# monoblink_pannel.net
KiCad netlist of a schematic drawn in EAGLE
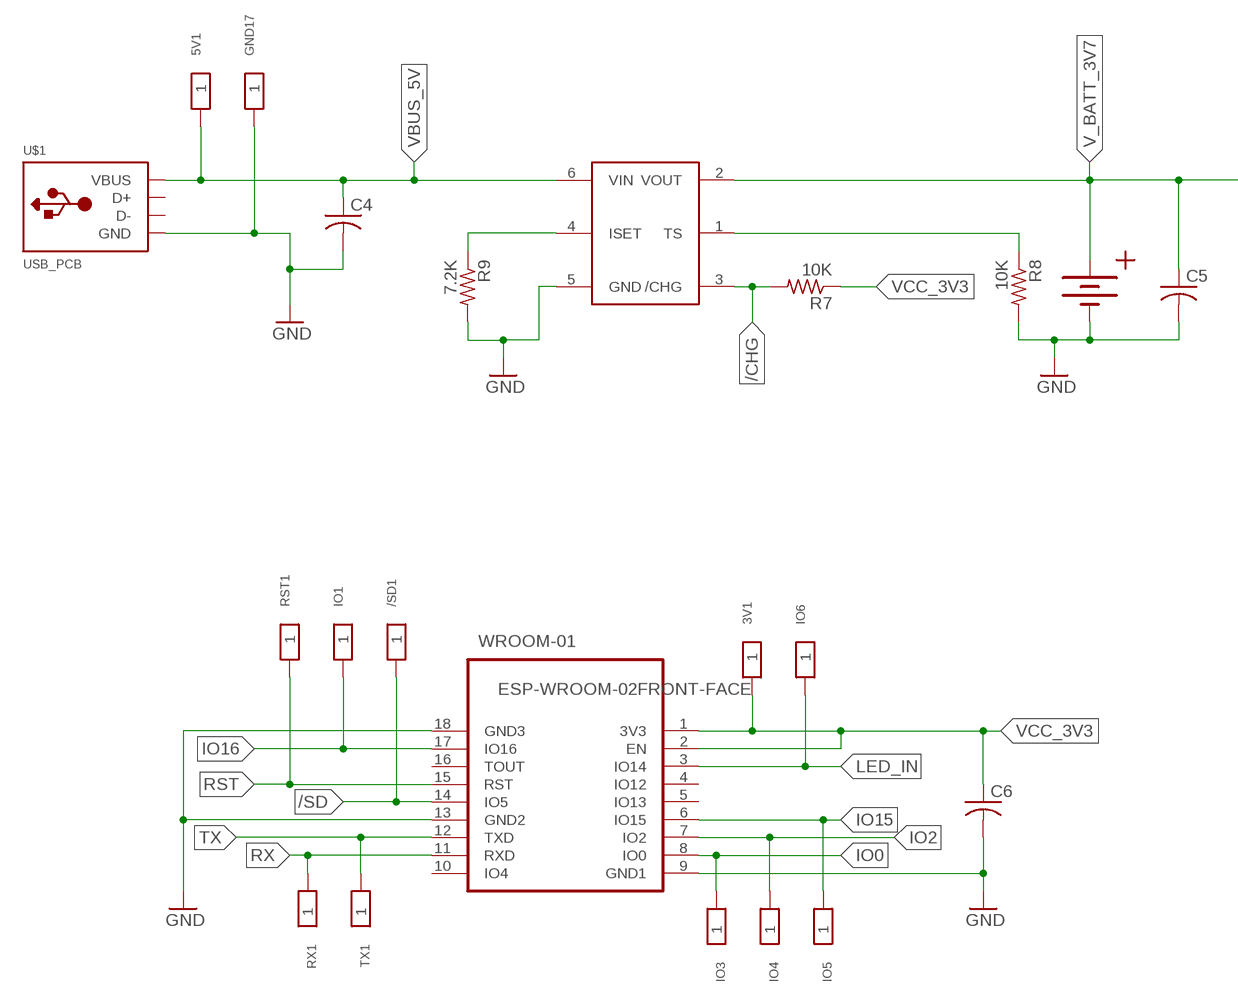
[diagram p0: schematic, sheet 1, part 1 of 2]
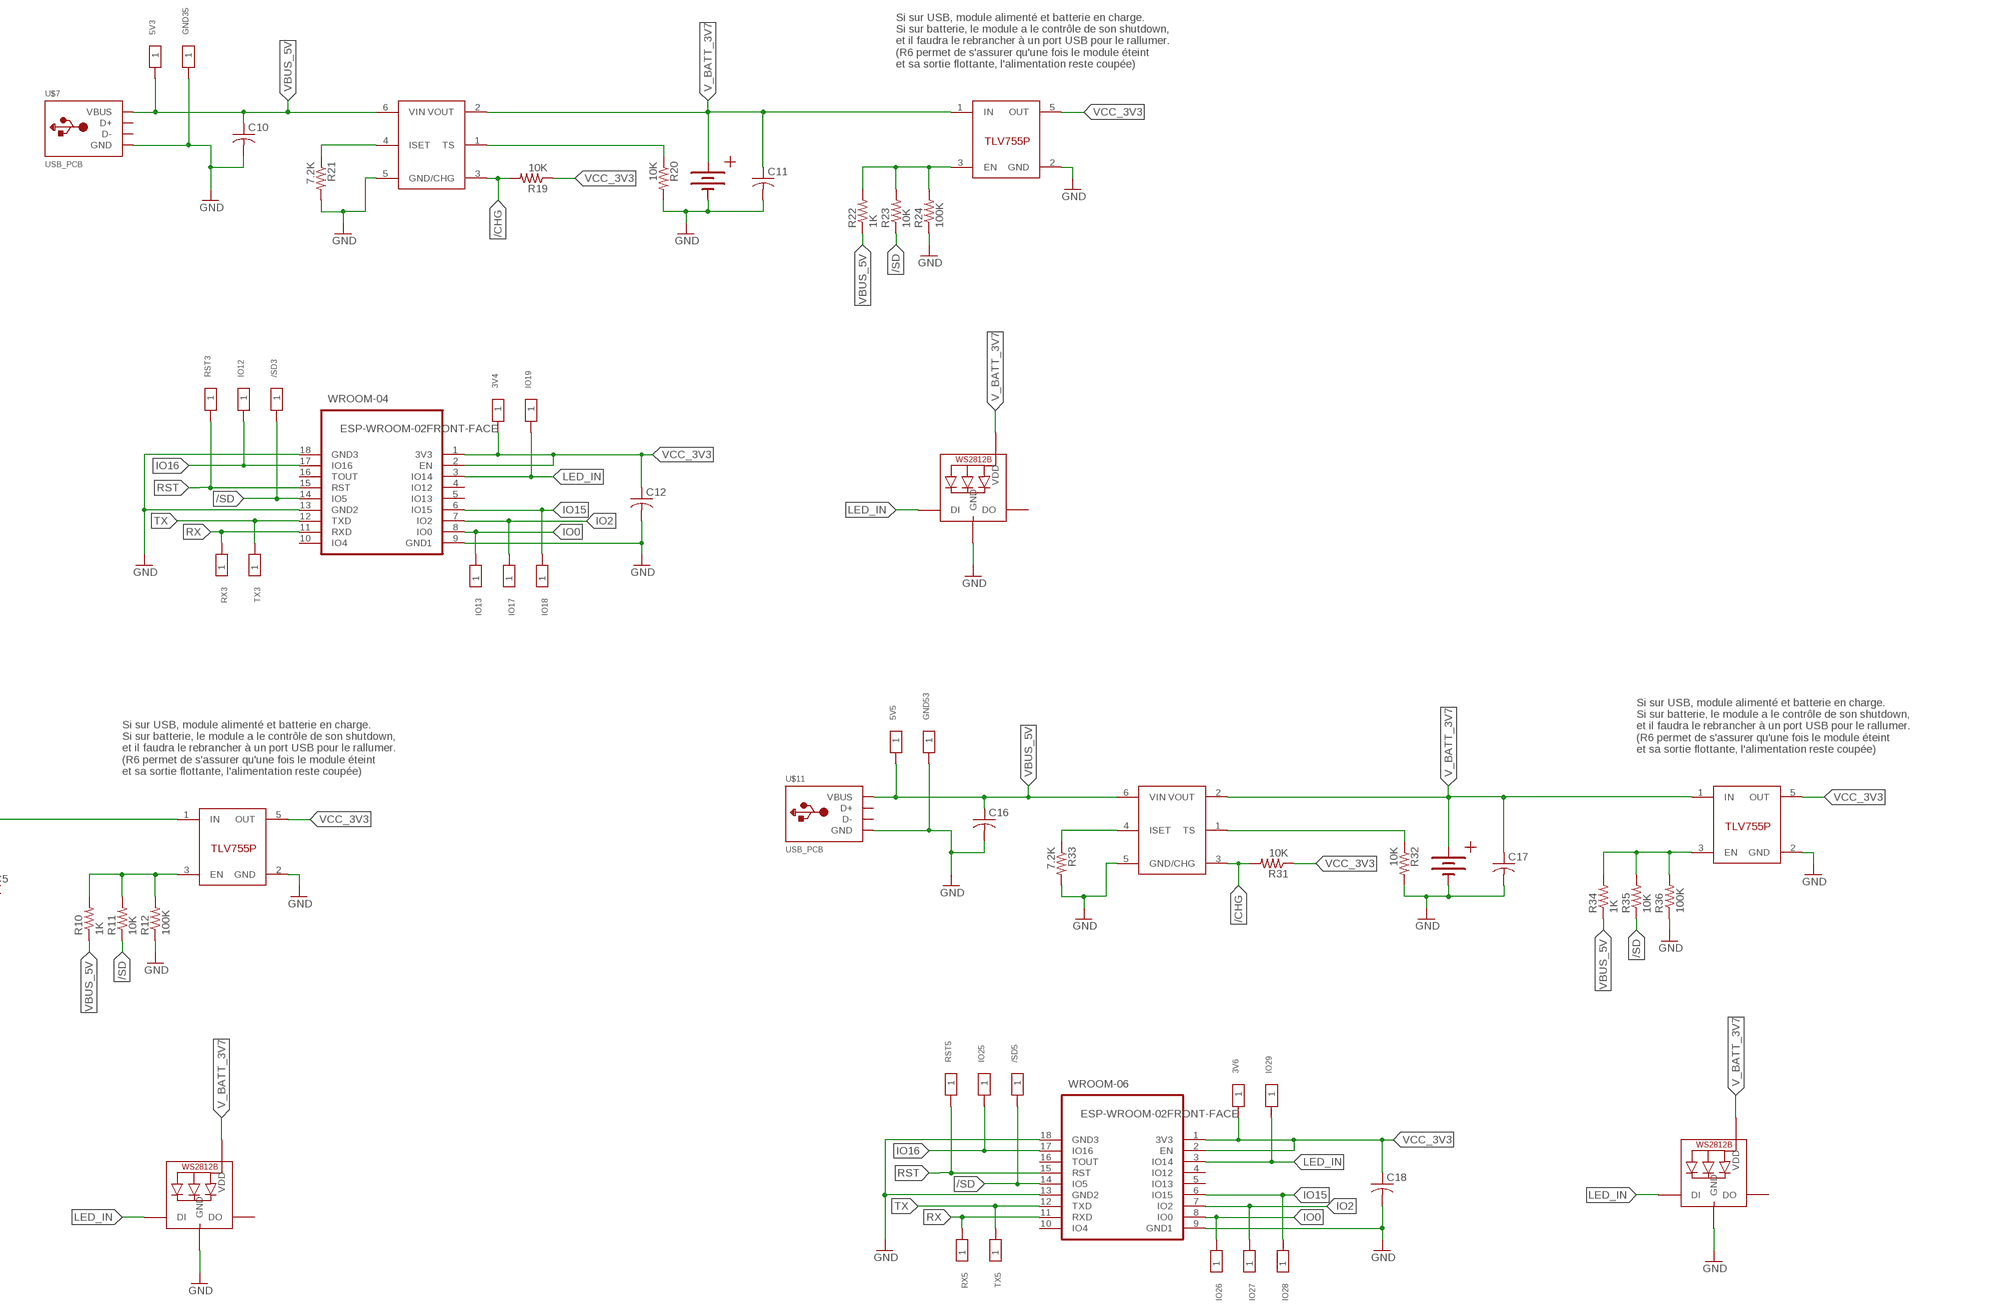
[diagram p1: schematic, sheet 1, part 2 of 2]

(export (version "E")
  (design (tool "Eeschema 10.0.6"))
  (components
    (comp (ref "/SD1")
      (value "TESTPAD_PROG")
      (footprint "eagle-import:TP1.5MM")
      (libsource (lib "eagle-import") (part "TESTPAD_PROG"))
    )
    (comp (ref "/SD3")
      (value "TESTPAD_PROG")
      (footprint "eagle-import:TP1.5MM")
      (libsource (lib "eagle-import") (part "TESTPAD_PROG"))
    )
    (comp (ref "/SD5")
      (value "TESTPAD_PROG")
      (footprint "eagle-import:TP1.5MM")
      (libsource (lib "eagle-import") (part "TESTPAD_PROG"))
    )
    (comp (ref "3V1")
      (value "TESTPAD_PROG")
      (footprint "eagle-import:TP1.5MM")
      (libsource (lib "eagle-import") (part "TESTPAD_PROG"))
    )
    (comp (ref "3V4")
      (value "TESTPAD_PROG")
      (footprint "eagle-import:TP1.5MM")
      (libsource (lib "eagle-import") (part "TESTPAD_PROG"))
    )
    (comp (ref "3V6")
      (value "TESTPAD_PROG")
      (footprint "eagle-import:TP1.5MM")
      (libsource (lib "eagle-import") (part "TESTPAD_PROG"))
    )
    (comp (ref "5V1")
      (value "TESTPAD_PROG")
      (footprint "eagle-import:TP1.5MM")
      (libsource (lib "eagle-import") (part "TESTPAD_PROG"))
    )
    (comp (ref "5V3")
      (value "TESTPAD_PROG")
      (footprint "eagle-import:TP1.5MM")
      (libsource (lib "eagle-import") (part "TESTPAD_PROG"))
    )
    (comp (ref "5V5")
      (value "TESTPAD_PROG")
      (footprint "eagle-import:TP1.5MM")
      (libsource (lib "eagle-import") (part "TESTPAD_PROG"))
    )
    (comp (ref "C4")
      (value "C-USC0603")
      (footprint "eagle-import:C0603")
      (libsource (lib "eagle-import") (part "C-USC0603"))
    )
    (comp (ref "C5")
      (value "C-USC0603")
      (footprint "eagle-import:C0603")
      (libsource (lib "eagle-import") (part "C-USC0603"))
    )
    (comp (ref "C6")
      (value "C-USC0603")
      (footprint "eagle-import:C0603")
      (libsource (lib "eagle-import") (part "C-USC0603"))
    )
    (comp (ref "C10")
      (value "C-USC0603")
      (footprint "eagle-import:C0603")
      (libsource (lib "eagle-import") (part "C-USC0603"))
    )
    (comp (ref "C11")
      (value "C-USC0603")
      (footprint "eagle-import:C0603")
      (libsource (lib "eagle-import") (part "C-USC0603"))
    )
    (comp (ref "C12")
      (value "C-USC0603")
      (footprint "eagle-import:C0603")
      (libsource (lib "eagle-import") (part "C-USC0603"))
    )
    (comp (ref "C16")
      (value "C-USC0603")
      (footprint "eagle-import:C0603")
      (libsource (lib "eagle-import") (part "C-USC0603"))
    )
    (comp (ref "C17")
      (value "C-USC0603")
      (footprint "eagle-import:C0603")
      (libsource (lib "eagle-import") (part "C-USC0603"))
    )
    (comp (ref "C18")
      (value "C-USC0603")
      (footprint "eagle-import:C0603")
      (libsource (lib "eagle-import") (part "C-USC0603"))
    )
    (comp (ref "CHG1")
      (value "BQ21040")
      (footprint "eagle-import:SOT23-6")
      (libsource (lib "eagle-import") (part "BQ21040"))
    )
    (comp (ref "CHG3")
      (value "BQ21040")
      (footprint "eagle-import:SOT23-6")
      (libsource (lib "eagle-import") (part "BQ21040"))
    )
    (comp (ref "CHG5")
      (value "BQ21040")
      (footprint "eagle-import:SOT23-6")
      (libsource (lib "eagle-import") (part "BQ21040"))
    )
    (comp (ref "GND17")
      (value "TESTPAD_PROG")
      (footprint "eagle-import:TP1.5MM")
      (libsource (lib "eagle-import") (part "TESTPAD_PROG"))
    )
    (comp (ref "GND35")
      (value "TESTPAD_PROG")
      (footprint "eagle-import:TP1.5MM")
      (libsource (lib "eagle-import") (part "TESTPAD_PROG"))
    )
    (comp (ref "GND53")
      (value "TESTPAD_PROG")
      (footprint "eagle-import:TP1.5MM")
      (libsource (lib "eagle-import") (part "TESTPAD_PROG"))
    )
    (comp (ref "IO1")
      (value "TESTPAD_PROG")
      (footprint "eagle-import:TP1.5MM")
      (libsource (lib "eagle-import") (part "TESTPAD_PROG"))
    )
    (comp (ref "IO3")
      (value "TESTPAD_PROG")
      (footprint "eagle-import:TP1.5MM")
      (libsource (lib "eagle-import") (part "TESTPAD_PROG"))
    )
    (comp (ref "IO4")
      (value "TESTPAD_PROG")
      (footprint "eagle-import:TP1.5MM")
      (libsource (lib "eagle-import") (part "TESTPAD_PROG"))
    )
    (comp (ref "IO5")
      (value "TESTPAD_PROG")
      (footprint "eagle-import:TP1.5MM")
      (libsource (lib "eagle-import") (part "TESTPAD_PROG"))
    )
    (comp (ref "IO6")
      (value "TESTPAD_PROG")
      (footprint "eagle-import:TP1.5MM")
      (libsource (lib "eagle-import") (part "TESTPAD_PROG"))
    )
    (comp (ref "IO12")
      (value "TESTPAD_PROG")
      (footprint "eagle-import:TP1.5MM")
      (libsource (lib "eagle-import") (part "TESTPAD_PROG"))
    )
    (comp (ref "IO13")
      (value "TESTPAD_PROG")
      (footprint "eagle-import:TP1.5MM")
      (libsource (lib "eagle-import") (part "TESTPAD_PROG"))
    )
    (comp (ref "IO17")
      (value "TESTPAD_PROG")
      (footprint "eagle-import:TP1.5MM")
      (libsource (lib "eagle-import") (part "TESTPAD_PROG"))
    )
    (comp (ref "IO18")
      (value "TESTPAD_PROG")
      (footprint "eagle-import:TP1.5MM")
      (libsource (lib "eagle-import") (part "TESTPAD_PROG"))
    )
    (comp (ref "IO19")
      (value "TESTPAD_PROG")
      (footprint "eagle-import:TP1.5MM")
      (libsource (lib "eagle-import") (part "TESTPAD_PROG"))
    )
    (comp (ref "IO25")
      (value "TESTPAD_PROG")
      (footprint "eagle-import:TP1.5MM")
      (libsource (lib "eagle-import") (part "TESTPAD_PROG"))
    )
    (comp (ref "IO26")
      (value "TESTPAD_PROG")
      (footprint "eagle-import:TP1.5MM")
      (libsource (lib "eagle-import") (part "TESTPAD_PROG"))
    )
    (comp (ref "IO27")
      (value "TESTPAD_PROG")
      (footprint "eagle-import:TP1.5MM")
      (libsource (lib "eagle-import") (part "TESTPAD_PROG"))
    )
    (comp (ref "IO28")
      (value "TESTPAD_PROG")
      (footprint "eagle-import:TP1.5MM")
      (libsource (lib "eagle-import") (part "TESTPAD_PROG"))
    )
    (comp (ref "IO29")
      (value "TESTPAD_PROG")
      (footprint "eagle-import:TP1.5MM")
      (libsource (lib "eagle-import") (part "TESTPAD_PROG"))
    )
    (comp (ref "LDO1")
      (value "TLV755P")
      (footprint "eagle-import:SOT23-5")
      (libsource (lib "eagle-import") (part "TLV755P"))
    )
    (comp (ref "LDO3")
      (value "TLV755P")
      (footprint "eagle-import:SOT23-5")
      (libsource (lib "eagle-import") (part "TLV755P"))
    )
    (comp (ref "LDO5")
      (value "TLV755P")
      (footprint "eagle-import:SOT23-5")
      (libsource (lib "eagle-import") (part "TLV755P"))
    )
    (comp (ref "LED1")
      (value "WS2812B5050")
      (footprint "eagle-import:WS2812B")
      (libsource (lib "eagle-import") (part "WS2812B5050"))
    )
    (comp (ref "LED3")
      (value "WS2812B5050")
      (footprint "eagle-import:WS2812B")
      (libsource (lib "eagle-import") (part "WS2812B5050"))
    )
    (comp (ref "LED5")
      (value "WS2812B5050")
      (footprint "eagle-import:WS2812B")
      (libsource (lib "eagle-import") (part "WS2812B5050"))
    )
    (comp (ref "R7")
      (value "10K")
      (footprint "eagle-import:R0603")
      (libsource (lib "eagle-import") (part "R-US_R0603"))
    )
    (comp (ref "R8")
      (value "10K")
      (footprint "eagle-import:R0603")
      (libsource (lib "eagle-import") (part "R-US_R0603"))
    )
    (comp (ref "R9")
      (value "7.2K")
      (footprint "eagle-import:R0603")
      (libsource (lib "eagle-import") (part "R-US_R0603"))
    )
    (comp (ref "R10")
      (value "1K")
      (footprint "eagle-import:R0603")
      (libsource (lib "eagle-import") (part "R-US_R0603"))
    )
    (comp (ref "R11")
      (value "10K")
      (footprint "eagle-import:R0603")
      (libsource (lib "eagle-import") (part "R-US_R0603"))
    )
    (comp (ref "R12")
      (value "100K")
      (footprint "eagle-import:R0603")
      (libsource (lib "eagle-import") (part "R-US_R0603"))
    )
    (comp (ref "R19")
      (value "10K")
      (footprint "eagle-import:R0603")
      (libsource (lib "eagle-import") (part "R-US_R0603"))
    )
    (comp (ref "R20")
      (value "10K")
      (footprint "eagle-import:R0603")
      (libsource (lib "eagle-import") (part "R-US_R0603"))
    )
    (comp (ref "R21")
      (value "7.2K")
      (footprint "eagle-import:R0603")
      (libsource (lib "eagle-import") (part "R-US_R0603"))
    )
    (comp (ref "R22")
      (value "1K")
      (footprint "eagle-import:R0603")
      (libsource (lib "eagle-import") (part "R-US_R0603"))
    )
    (comp (ref "R23")
      (value "10K")
      (footprint "eagle-import:R0603")
      (libsource (lib "eagle-import") (part "R-US_R0603"))
    )
    (comp (ref "R24")
      (value "100K")
      (footprint "eagle-import:R0603")
      (libsource (lib "eagle-import") (part "R-US_R0603"))
    )
    (comp (ref "R31")
      (value "10K")
      (footprint "eagle-import:R0603")
      (libsource (lib "eagle-import") (part "R-US_R0603"))
    )
    (comp (ref "R32")
      (value "10K")
      (footprint "eagle-import:R0603")
      (libsource (lib "eagle-import") (part "R-US_R0603"))
    )
    (comp (ref "R33")
      (value "7.2K")
      (footprint "eagle-import:R0603")
      (libsource (lib "eagle-import") (part "R-US_R0603"))
    )
    (comp (ref "R34")
      (value "1K")
      (footprint "eagle-import:R0603")
      (libsource (lib "eagle-import") (part "R-US_R0603"))
    )
    (comp (ref "R35")
      (value "10K")
      (footprint "eagle-import:R0603")
      (libsource (lib "eagle-import") (part "R-US_R0603"))
    )
    (comp (ref "R36")
      (value "100K")
      (footprint "eagle-import:R0603")
      (libsource (lib "eagle-import") (part "R-US_R0603"))
    )
    (comp (ref "RST1")
      (value "TESTPAD_PROG")
      (footprint "eagle-import:TP1.5MM")
      (libsource (lib "eagle-import") (part "TESTPAD_PROG"))
    )
    (comp (ref "RST3")
      (value "TESTPAD_PROG")
      (footprint "eagle-import:TP1.5MM")
      (libsource (lib "eagle-import") (part "TESTPAD_PROG"))
    )
    (comp (ref "RST5")
      (value "TESTPAD_PROG")
      (footprint "eagle-import:TP1.5MM")
      (libsource (lib "eagle-import") (part "TESTPAD_PROG"))
    )
    (comp (ref "RX1")
      (value "TESTPAD_PROG")
      (footprint "eagle-import:TP1.5MM")
      (libsource (lib "eagle-import") (part "TESTPAD_PROG"))
    )
    (comp (ref "RX3")
      (value "TESTPAD_PROG")
      (footprint "eagle-import:TP1.5MM")
      (libsource (lib "eagle-import") (part "TESTPAD_PROG"))
    )
    (comp (ref "RX5")
      (value "TESTPAD_PROG")
      (footprint "eagle-import:TP1.5MM")
      (libsource (lib "eagle-import") (part "TESTPAD_PROG"))
    )
    (comp (ref "TX1")
      (value "TESTPAD_PROG")
      (footprint "eagle-import:TP1.5MM")
      (libsource (lib "eagle-import") (part "TESTPAD_PROG"))
    )
    (comp (ref "TX3")
      (value "TESTPAD_PROG")
      (footprint "eagle-import:TP1.5MM")
      (libsource (lib "eagle-import") (part "TESTPAD_PROG"))
    )
    (comp (ref "TX5")
      (value "TESTPAD_PROG")
      (footprint "eagle-import:TP1.5MM")
      (libsource (lib "eagle-import") (part "TESTPAD_PROG"))
    )
    (comp (ref "U$1")
      (value "USB_PCB")
      (footprint "eagle-import:USB_PADS")
      (libsource (lib "eagle-import") (part "USB_PCB"))
    )
    (comp (ref "U$3")
      (value "BATT")
      (footprint "eagle-import:BATT_CON")
      (libsource (lib "eagle-import") (part "BATT"))
    )
    (comp (ref "U$7")
      (value "USB_PCB")
      (footprint "eagle-import:USB_PADS")
      (libsource (lib "eagle-import") (part "USB_PCB"))
    )
    (comp (ref "U$8")
      (value "BATT")
      (footprint "eagle-import:BATT_CON")
      (libsource (lib "eagle-import") (part "BATT"))
    )
    (comp (ref "U$11")
      (value "USB_PCB")
      (footprint "eagle-import:USB_PADS")
      (libsource (lib "eagle-import") (part "USB_PCB"))
    )
    (comp (ref "U$12")
      (value "BATT")
      (footprint "eagle-import:BATT_CON")
      (libsource (lib "eagle-import") (part "BATT"))
    )
    (comp (ref "WROOM-01")
      (value "ESP-WROOM-02FRONT-FACE")
      (footprint "eagle-import:FRONT-FACE")
      (libsource (lib "eagle-import") (part "ESP-WROOM-02FRONT-FACE"))
    )
    (comp (ref "WROOM-04")
      (value "ESP-WROOM-02FRONT-FACE")
      (footprint "eagle-import:FRONT-FACE")
      (libsource (lib "eagle-import") (part "ESP-WROOM-02FRONT-FACE"))
    )
    (comp (ref "WROOM-06")
      (value "ESP-WROOM-02FRONT-FACE")
      (footprint "eagle-import:FRONT-FACE")
      (libsource (lib "eagle-import") (part "ESP-WROOM-02FRONT-FACE"))
    )
  )
  (nets
    (net (code "1") (name "GND") (class "Default")
      (node (ref "C10") (pin "2") (pinfunction "2_2") (pintype "passive"))
      (node (ref "C11") (pin "2") (pinfunction "2_2") (pintype "passive"))
      (node (ref "C12") (pin "2") (pinfunction "2_2") (pintype "passive"))
      (node (ref "C16") (pin "2") (pinfunction "2_2") (pintype "passive"))
      (node (ref "C17") (pin "2") (pinfunction "2_2") (pintype "passive"))
      (node (ref "C18") (pin "2") (pinfunction "2_2") (pintype "passive"))
      (node (ref "C4") (pin "2") (pinfunction "2_2") (pintype "passive"))
      (node (ref "C5") (pin "2") (pinfunction "2_2") (pintype "passive"))
      (node (ref "C6") (pin "2") (pinfunction "2_2") (pintype "passive"))
      (node (ref "CHG1") (pin "5") (pinfunction "GND_5") (pintype "bidirectional"))
      (node (ref "CHG3") (pin "5") (pinfunction "GND_5") (pintype "bidirectional"))
      (node (ref "CHG5") (pin "5") (pinfunction "GND_5") (pintype "bidirectional"))
      (node (ref "GND17") (pin "1") (pinfunction "1_1") (pintype "bidirectional"))
      (node (ref "GND35") (pin "1") (pinfunction "1_1") (pintype "bidirectional"))
      (node (ref "GND53") (pin "1") (pinfunction "1_1") (pintype "bidirectional"))
      (node (ref "LDO1") (pin "2") (pinfunction "GND_2") (pintype "bidirectional"))
      (node (ref "LDO3") (pin "2") (pinfunction "GND_2") (pintype "bidirectional"))
      (node (ref "LDO5") (pin "2") (pinfunction "GND_2") (pintype "bidirectional"))
      (node (ref "LED1") (pin "3-GND") (pinfunction "GND_3-GND") (pintype "power_in"))
      (node (ref "LED3") (pin "3-GND") (pinfunction "GND_3-GND") (pintype "power_in"))
      (node (ref "LED5") (pin "3-GND") (pinfunction "GND_3-GND") (pintype "power_in"))
      (node (ref "R12") (pin "1") (pinfunction "1_1") (pintype "passive"))
      (node (ref "R20") (pin "2") (pinfunction "2_2") (pintype "passive"))
      (node (ref "R21") (pin "2") (pinfunction "2_2") (pintype "passive"))
      (node (ref "R24") (pin "1") (pinfunction "1_1") (pintype "passive"))
      (node (ref "R32") (pin "2") (pinfunction "2_2") (pintype "passive"))
      (node (ref "R33") (pin "2") (pinfunction "2_2") (pintype "passive"))
      (node (ref "R36") (pin "1") (pinfunction "1_1") (pintype "passive"))
      (node (ref "R8") (pin "2") (pinfunction "2_2") (pintype "passive"))
      (node (ref "R9") (pin "2") (pinfunction "2_2") (pintype "passive"))
      (node (ref "U$1") (pin "GND") (pinfunction "GND_GND") (pintype "power_in"))
      (node (ref "U$11") (pin "GND") (pinfunction "GND_GND") (pintype "power_in"))
      (node (ref "U$12") (pin "V-") (pinfunction "-_V-") (pintype "power_in"))
      (node (ref "U$3") (pin "V-") (pinfunction "-_V-") (pintype "power_in"))
      (node (ref "U$7") (pin "GND") (pinfunction "GND_GND") (pintype "power_in"))
      (node (ref "U$8") (pin "V-") (pinfunction "-_V-") (pintype "power_in"))
      (node (ref "WROOM-01") (pin "13") (pinfunction "GND2_13") (pintype "power_in"))
      (node (ref "WROOM-01") (pin "18") (pinfunction "GND3_18") (pintype "power_in"))
      (node (ref "WROOM-01") (pin "9") (pinfunction "GND1_9") (pintype "power_in"))
      (node (ref "WROOM-04") (pin "13") (pinfunction "GND2_13") (pintype "power_in"))
      (node (ref "WROOM-04") (pin "18") (pinfunction "GND3_18") (pintype "power_in"))
      (node (ref "WROOM-04") (pin "9") (pinfunction "GND1_9") (pintype "power_in"))
      (node (ref "WROOM-06") (pin "13") (pinfunction "GND2_13") (pintype "power_in"))
      (node (ref "WROOM-06") (pin "18") (pinfunction "GND3_18") (pintype "power_in"))
      (node (ref "WROOM-06") (pin "9") (pinfunction "GND1_9") (pintype "power_in"))
    )
    (net (code "2") (name "IO0") (class "Default")
      (node (ref "IO13") (pin "1") (pinfunction "1_1") (pintype "bidirectional"))
      (node (ref "IO26") (pin "1") (pinfunction "1_1") (pintype "bidirectional"))
      (node (ref "IO3") (pin "1") (pinfunction "1_1") (pintype "bidirectional"))
      (node (ref "WROOM-01") (pin "8") (pinfunction "IO0_8") (pintype "bidirectional"))
      (node (ref "WROOM-04") (pin "8") (pinfunction "IO0_8") (pintype "bidirectional"))
      (node (ref "WROOM-06") (pin "8") (pinfunction "IO0_8") (pintype "bidirectional"))
    )
    (net (code "3") (name "IO2") (class "Default")
      (node (ref "IO17") (pin "1") (pinfunction "1_1") (pintype "bidirectional"))
      (node (ref "IO27") (pin "1") (pinfunction "1_1") (pintype "bidirectional"))
      (node (ref "IO4") (pin "1") (pinfunction "1_1") (pintype "bidirectional"))
      (node (ref "WROOM-01") (pin "7") (pinfunction "IO2_7") (pintype "bidirectional"))
      (node (ref "WROOM-04") (pin "7") (pinfunction "IO2_7") (pintype "bidirectional"))
      (node (ref "WROOM-06") (pin "7") (pinfunction "IO2_7") (pintype "bidirectional"))
    )
    (net (code "4") (name "IO15") (class "Default")
      (node (ref "IO18") (pin "1") (pinfunction "1_1") (pintype "bidirectional"))
      (node (ref "IO28") (pin "1") (pinfunction "1_1") (pintype "bidirectional"))
      (node (ref "IO5") (pin "1") (pinfunction "1_1") (pintype "bidirectional"))
      (node (ref "WROOM-01") (pin "6") (pinfunction "IO15_6") (pintype "bidirectional"))
      (node (ref "WROOM-04") (pin "6") (pinfunction "IO15_6") (pintype "bidirectional"))
      (node (ref "WROOM-06") (pin "6") (pinfunction "IO15_6") (pintype "bidirectional"))
    )
    (net (code "5") (name "IO16") (class "Default")
      (node (ref "IO1") (pin "1") (pinfunction "1_1") (pintype "bidirectional"))
      (node (ref "IO12") (pin "1") (pinfunction "1_1") (pintype "bidirectional"))
      (node (ref "IO25") (pin "1") (pinfunction "1_1") (pintype "bidirectional"))
      (node (ref "WROOM-01") (pin "17") (pinfunction "IO16_17") (pintype "bidirectional"))
      (node (ref "WROOM-04") (pin "17") (pinfunction "IO16_17") (pintype "bidirectional"))
      (node (ref "WROOM-06") (pin "17") (pinfunction "IO16_17") (pintype "bidirectional"))
    )
    (net (code "6") (name "LED_IN") (class "Default")
      (node (ref "IO19") (pin "1") (pinfunction "1_1") (pintype "bidirectional"))
      (node (ref "IO29") (pin "1") (pinfunction "1_1") (pintype "bidirectional"))
      (node (ref "IO6") (pin "1") (pinfunction "1_1") (pintype "bidirectional"))
      (node (ref "LED1") (pin "4-DIN") (pinfunction "DI_4-DIN") (pintype "input"))
      (node (ref "LED3") (pin "4-DIN") (pinfunction "DI_4-DIN") (pintype "input"))
      (node (ref "LED5") (pin "4-DIN") (pinfunction "DI_4-DIN") (pintype "input"))
      (node (ref "WROOM-01") (pin "3") (pinfunction "IO14_3") (pintype "bidirectional"))
      (node (ref "WROOM-04") (pin "3") (pinfunction "IO14_3") (pintype "bidirectional"))
      (node (ref "WROOM-06") (pin "3") (pinfunction "IO14_3") (pintype "bidirectional"))
    )
    (net (code "7") (name "Net-(CHG1-ISET)") (class "Default")
      (node (ref "CHG1") (pin "4") (pinfunction "ISET_4") (pintype "bidirectional"))
      (node (ref "R9") (pin "1") (pinfunction "1_1") (pintype "passive"))
    )
    (net (code "8") (name "Net-(CHG1-TS)") (class "Default")
      (node (ref "CHG1") (pin "1") (pinfunction "TS_1") (pintype "bidirectional"))
      (node (ref "R8") (pin "1") (pinfunction "1_1") (pintype "passive"))
    )
    (net (code "9") (name "Net-(CHG3-ISET)") (class "Default")
      (node (ref "CHG3") (pin "4") (pinfunction "ISET_4") (pintype "bidirectional"))
      (node (ref "R21") (pin "1") (pinfunction "1_1") (pintype "passive"))
    )
    (net (code "10") (name "Net-(CHG3-TS)") (class "Default")
      (node (ref "CHG3") (pin "1") (pinfunction "TS_1") (pintype "bidirectional"))
      (node (ref "R20") (pin "1") (pinfunction "1_1") (pintype "passive"))
    )
    (net (code "11") (name "Net-(CHG5-ISET)") (class "Default")
      (node (ref "CHG5") (pin "4") (pinfunction "ISET_4") (pintype "bidirectional"))
      (node (ref "R33") (pin "1") (pinfunction "1_1") (pintype "passive"))
    )
    (net (code "12") (name "Net-(CHG5-TS)") (class "Default")
      (node (ref "CHG5") (pin "1") (pinfunction "TS_1") (pintype "bidirectional"))
      (node (ref "R32") (pin "1") (pinfunction "1_1") (pintype "passive"))
    )
    (net (code "13") (name "Net-(LDO1-EN)") (class "Default")
      (node (ref "LDO1") (pin "3") (pinfunction "EN_3") (pintype "bidirectional"))
      (node (ref "R10") (pin "2") (pinfunction "2_2") (pintype "passive"))
      (node (ref "R11") (pin "2") (pinfunction "2_2") (pintype "passive"))
      (node (ref "R12") (pin "2") (pinfunction "2_2") (pintype "passive"))
    )
    (net (code "14") (name "Net-(LDO3-EN)") (class "Default")
      (node (ref "LDO3") (pin "3") (pinfunction "EN_3") (pintype "bidirectional"))
      (node (ref "R22") (pin "2") (pinfunction "2_2") (pintype "passive"))
      (node (ref "R23") (pin "2") (pinfunction "2_2") (pintype "passive"))
      (node (ref "R24") (pin "2") (pinfunction "2_2") (pintype "passive"))
    )
    (net (code "15") (name "Net-(LDO5-EN)") (class "Default")
      (node (ref "LDO5") (pin "3") (pinfunction "EN_3") (pintype "bidirectional"))
      (node (ref "R34") (pin "2") (pinfunction "2_2") (pintype "passive"))
      (node (ref "R35") (pin "2") (pinfunction "2_2") (pintype "passive"))
      (node (ref "R36") (pin "2") (pinfunction "2_2") (pintype "passive"))
    )
    (net (code "16") (name "RST") (class "Default")
      (node (ref "RST1") (pin "1") (pinfunction "1_1") (pintype "bidirectional"))
      (node (ref "RST3") (pin "1") (pinfunction "1_1") (pintype "bidirectional"))
      (node (ref "RST5") (pin "1") (pinfunction "1_1") (pintype "bidirectional"))
      (node (ref "WROOM-01") (pin "15") (pinfunction "RST_15") (pintype "bidirectional"))
      (node (ref "WROOM-04") (pin "15") (pinfunction "RST_15") (pintype "bidirectional"))
      (node (ref "WROOM-06") (pin "15") (pinfunction "RST_15") (pintype "bidirectional"))
    )
    (net (code "17") (name "RX") (class "Default")
      (node (ref "RX1") (pin "1") (pinfunction "1_1") (pintype "bidirectional"))
      (node (ref "RX3") (pin "1") (pinfunction "1_1") (pintype "bidirectional"))
      (node (ref "RX5") (pin "1") (pinfunction "1_1") (pintype "bidirectional"))
      (node (ref "WROOM-01") (pin "11") (pinfunction "RXD_11") (pintype "bidirectional"))
      (node (ref "WROOM-04") (pin "11") (pinfunction "RXD_11") (pintype "bidirectional"))
      (node (ref "WROOM-06") (pin "11") (pinfunction "RXD_11") (pintype "bidirectional"))
    )
    (net (code "18") (name "TX") (class "Default")
      (node (ref "TX1") (pin "1") (pinfunction "1_1") (pintype "bidirectional"))
      (node (ref "TX3") (pin "1") (pinfunction "1_1") (pintype "bidirectional"))
      (node (ref "TX5") (pin "1") (pinfunction "1_1") (pintype "bidirectional"))
      (node (ref "WROOM-01") (pin "12") (pinfunction "TXD_12") (pintype "bidirectional"))
      (node (ref "WROOM-04") (pin "12") (pinfunction "TXD_12") (pintype "bidirectional"))
      (node (ref "WROOM-06") (pin "12") (pinfunction "TXD_12") (pintype "bidirectional"))
    )
    (net (code "19") (name "VBUS_5V") (class "Default")
      (node (ref "5V1") (pin "1") (pinfunction "1_1") (pintype "bidirectional"))
      (node (ref "5V3") (pin "1") (pinfunction "1_1") (pintype "bidirectional"))
      (node (ref "5V5") (pin "1") (pinfunction "1_1") (pintype "bidirectional"))
      (node (ref "C10") (pin "1") (pinfunction "1_1") (pintype "passive"))
      (node (ref "C16") (pin "1") (pinfunction "1_1") (pintype "passive"))
      (node (ref "C4") (pin "1") (pinfunction "1_1") (pintype "passive"))
      (node (ref "CHG1") (pin "6") (pinfunction "VIN_6") (pintype "bidirectional"))
      (node (ref "CHG3") (pin "6") (pinfunction "VIN_6") (pintype "bidirectional"))
      (node (ref "CHG5") (pin "6") (pinfunction "VIN_6") (pintype "bidirectional"))
      (node (ref "R10") (pin "1") (pinfunction "1_1") (pintype "passive"))
      (node (ref "R22") (pin "1") (pinfunction "1_1") (pintype "passive"))
      (node (ref "R34") (pin "1") (pinfunction "1_1") (pintype "passive"))
      (node (ref "U$1") (pin "V_SUPPLY") (pinfunction "VBUS_V_SUPPLY") (pintype "power_in"))
      (node (ref "U$11") (pin "V_SUPPLY") (pinfunction "VBUS_V_SUPPLY") (pintype "power_in"))
      (node (ref "U$7") (pin "V_SUPPLY") (pinfunction "VBUS_V_SUPPLY") (pintype "power_in"))
    )
    (net (code "20") (name "VCC_3V3") (class "Default")
      (node (ref "3V1") (pin "1") (pinfunction "1_1") (pintype "bidirectional"))
      (node (ref "3V4") (pin "1") (pinfunction "1_1") (pintype "bidirectional"))
      (node (ref "3V6") (pin "1") (pinfunction "1_1") (pintype "bidirectional"))
      (node (ref "C12") (pin "1") (pinfunction "1_1") (pintype "passive"))
      (node (ref "C18") (pin "1") (pinfunction "1_1") (pintype "passive"))
      (node (ref "C6") (pin "1") (pinfunction "1_1") (pintype "passive"))
      (node (ref "LDO1") (pin "5") (pinfunction "OUT_5") (pintype "bidirectional"))
      (node (ref "LDO3") (pin "5") (pinfunction "OUT_5") (pintype "bidirectional"))
      (node (ref "LDO5") (pin "5") (pinfunction "OUT_5") (pintype "bidirectional"))
      (node (ref "R19") (pin "1") (pinfunction "1_1") (pintype "passive"))
      (node (ref "R31") (pin "1") (pinfunction "1_1") (pintype "passive"))
      (node (ref "R7") (pin "1") (pinfunction "1_1") (pintype "passive"))
      (node (ref "WROOM-01") (pin "1") (pinfunction "3V3_1") (pintype "power_in"))
      (node (ref "WROOM-01") (pin "2") (pinfunction "EN_2") (pintype "bidirectional"))
      (node (ref "WROOM-04") (pin "1") (pinfunction "3V3_1") (pintype "power_in"))
      (node (ref "WROOM-04") (pin "2") (pinfunction "EN_2") (pintype "bidirectional"))
      (node (ref "WROOM-06") (pin "1") (pinfunction "3V3_1") (pintype "power_in"))
      (node (ref "WROOM-06") (pin "2") (pinfunction "EN_2") (pintype "bidirectional"))
    )
    (net (code "21") (name "V_BATT_3V7") (class "Default")
      (node (ref "C11") (pin "1") (pinfunction "1_1") (pintype "passive"))
      (node (ref "C17") (pin "1") (pinfunction "1_1") (pintype "passive"))
      (node (ref "C5") (pin "1") (pinfunction "1_1") (pintype "passive"))
      (node (ref "CHG1") (pin "2") (pinfunction "VOUT_2") (pintype "bidirectional"))
      (node (ref "CHG3") (pin "2") (pinfunction "VOUT_2") (pintype "bidirectional"))
      (node (ref "CHG5") (pin "2") (pinfunction "VOUT_2") (pintype "bidirectional"))
      (node (ref "LDO1") (pin "1") (pinfunction "IN_1") (pintype "bidirectional"))
      (node (ref "LDO3") (pin "1") (pinfunction "IN_1") (pintype "bidirectional"))
      (node (ref "LDO5") (pin "1") (pinfunction "IN_1") (pintype "bidirectional"))
      (node (ref "LED1") (pin "1-VDD") (pinfunction "VDD_1-VDD") (pintype "power_in"))
      (node (ref "LED3") (pin "1-VDD") (pinfunction "VDD_1-VDD") (pintype "power_in"))
      (node (ref "LED5") (pin "1-VDD") (pinfunction "VDD_1-VDD") (pintype "power_in"))
      (node (ref "U$12") (pin "V+") (pinfunction "+_V+") (pintype "power_in"))
      (node (ref "U$3") (pin "V+") (pinfunction "+_V+") (pintype "power_in"))
      (node (ref "U$8") (pin "V+") (pinfunction "+_V+") (pintype "power_in"))
    )
    (net (code "22") (name "unconnected-(LED1-DO-Pad2-DOUT)") (class "Default")
      (node (ref "LED1") (pin "2-DOUT") (pinfunction "DO_2-DOUT") (pintype "output"))
    )
    (net (code "23") (name "unconnected-(LED3-DO-Pad2-DOUT)") (class "Default")
      (node (ref "LED3") (pin "2-DOUT") (pinfunction "DO_2-DOUT") (pintype "output"))
    )
    (net (code "24") (name "unconnected-(LED5-DO-Pad2-DOUT)") (class "Default")
      (node (ref "LED5") (pin "2-DOUT") (pinfunction "DO_2-DOUT") (pintype "output"))
    )
    (net (code "25") (name "unconnected-(U$1-PadD+)") (class "Default")
      (node (ref "U$1") (pin "D+") (pinfunction "D+_D+") (pintype "bidirectional"))
    )
    (net (code "26") (name "unconnected-(U$1-PadD-)") (class "Default")
      (node (ref "U$1") (pin "D-") (pinfunction "D-_D-") (pintype "bidirectional"))
    )
    (net (code "27") (name "unconnected-(U$7-PadD+)") (class "Default")
      (node (ref "U$7") (pin "D+") (pinfunction "D+_D+") (pintype "bidirectional"))
    )
    (net (code "28") (name "unconnected-(U$7-PadD-)") (class "Default")
      (node (ref "U$7") (pin "D-") (pinfunction "D-_D-") (pintype "bidirectional"))
    )
    (net (code "29") (name "unconnected-(U$11-PadD+)") (class "Default")
      (node (ref "U$11") (pin "D+") (pinfunction "D+_D+") (pintype "bidirectional"))
    )
    (net (code "30") (name "unconnected-(U$11-PadD-)") (class "Default")
      (node (ref "U$11") (pin "D-") (pinfunction "D-_D-") (pintype "bidirectional"))
    )
    (net (code "31") (name "unconnected-(WROOM-01-IO4-Pad10)") (class "Default")
      (node (ref "WROOM-01") (pin "10") (pinfunction "IO4_10") (pintype "bidirectional"))
    )
    (net (code "32") (name "unconnected-(WROOM-01-IO12-Pad4)") (class "Default")
      (node (ref "WROOM-01") (pin "4") (pinfunction "IO12_4") (pintype "bidirectional"))
    )
    (net (code "33") (name "unconnected-(WROOM-01-IO13-Pad5)") (class "Default")
      (node (ref "WROOM-01") (pin "5") (pinfunction "IO13_5") (pintype "bidirectional"))
    )
    (net (code "34") (name "unconnected-(WROOM-01-TOUT-Pad16)") (class "Default")
      (node (ref "WROOM-01") (pin "16") (pinfunction "TOUT_16") (pintype "bidirectional"))
    )
    (net (code "35") (name "unconnected-(WROOM-04-IO4-Pad10)") (class "Default")
      (node (ref "WROOM-04") (pin "10") (pinfunction "IO4_10") (pintype "bidirectional"))
    )
    (net (code "36") (name "unconnected-(WROOM-04-IO12-Pad4)") (class "Default")
      (node (ref "WROOM-04") (pin "4") (pinfunction "IO12_4") (pintype "bidirectional"))
    )
    (net (code "37") (name "unconnected-(WROOM-04-IO13-Pad5)") (class "Default")
      (node (ref "WROOM-04") (pin "5") (pinfunction "IO13_5") (pintype "bidirectional"))
    )
    (net (code "38") (name "unconnected-(WROOM-04-TOUT-Pad16)") (class "Default")
      (node (ref "WROOM-04") (pin "16") (pinfunction "TOUT_16") (pintype "bidirectional"))
    )
    (net (code "39") (name "unconnected-(WROOM-06-IO4-Pad10)") (class "Default")
      (node (ref "WROOM-06") (pin "10") (pinfunction "IO4_10") (pintype "bidirectional"))
    )
    (net (code "40") (name "unconnected-(WROOM-06-IO12-Pad4)") (class "Default")
      (node (ref "WROOM-06") (pin "4") (pinfunction "IO12_4") (pintype "bidirectional"))
    )
    (net (code "41") (name "unconnected-(WROOM-06-IO13-Pad5)") (class "Default")
      (node (ref "WROOM-06") (pin "5") (pinfunction "IO13_5") (pintype "bidirectional"))
    )
    (net (code "42") (name "unconnected-(WROOM-06-TOUT-Pad16)") (class "Default")
      (node (ref "WROOM-06") (pin "16") (pinfunction "TOUT_16") (pintype "bidirectional"))
    )
    (net (code "43") (name "{slash}CHG") (class "Default")
      (node (ref "CHG1") (pin "3") (pinfunction "/CHG_3") (pintype "bidirectional"))
      (node (ref "CHG3") (pin "3") (pinfunction "/CHG_3") (pintype "bidirectional"))
      (node (ref "CHG5") (pin "3") (pinfunction "/CHG_3") (pintype "bidirectional"))
      (node (ref "R19") (pin "2") (pinfunction "2_2") (pintype "passive"))
      (node (ref "R31") (pin "2") (pinfunction "2_2") (pintype "passive"))
      (node (ref "R7") (pin "2") (pinfunction "2_2") (pintype "passive"))
    )
    (net (code "44") (name "{slash}SD") (class "Default")
      (node (ref "/SD1") (pin "1") (pinfunction "1_1") (pintype "bidirectional"))
      (node (ref "/SD3") (pin "1") (pinfunction "1_1") (pintype "bidirectional"))
      (node (ref "/SD5") (pin "1") (pinfunction "1_1") (pintype "bidirectional"))
      (node (ref "R11") (pin "1") (pinfunction "1_1") (pintype "passive"))
      (node (ref "R23") (pin "1") (pinfunction "1_1") (pintype "passive"))
      (node (ref "R35") (pin "1") (pinfunction "1_1") (pintype "passive"))
      (node (ref "WROOM-01") (pin "14") (pinfunction "IO5_14") (pintype "open_collector"))
      (node (ref "WROOM-04") (pin "14") (pinfunction "IO5_14") (pintype "open_collector"))
      (node (ref "WROOM-06") (pin "14") (pinfunction "IO5_14") (pintype "open_collector"))
    )
  )
)
